# 000_BBB_Pinouts.net
KiCad netlist of a schematic drawn in Altium Designer
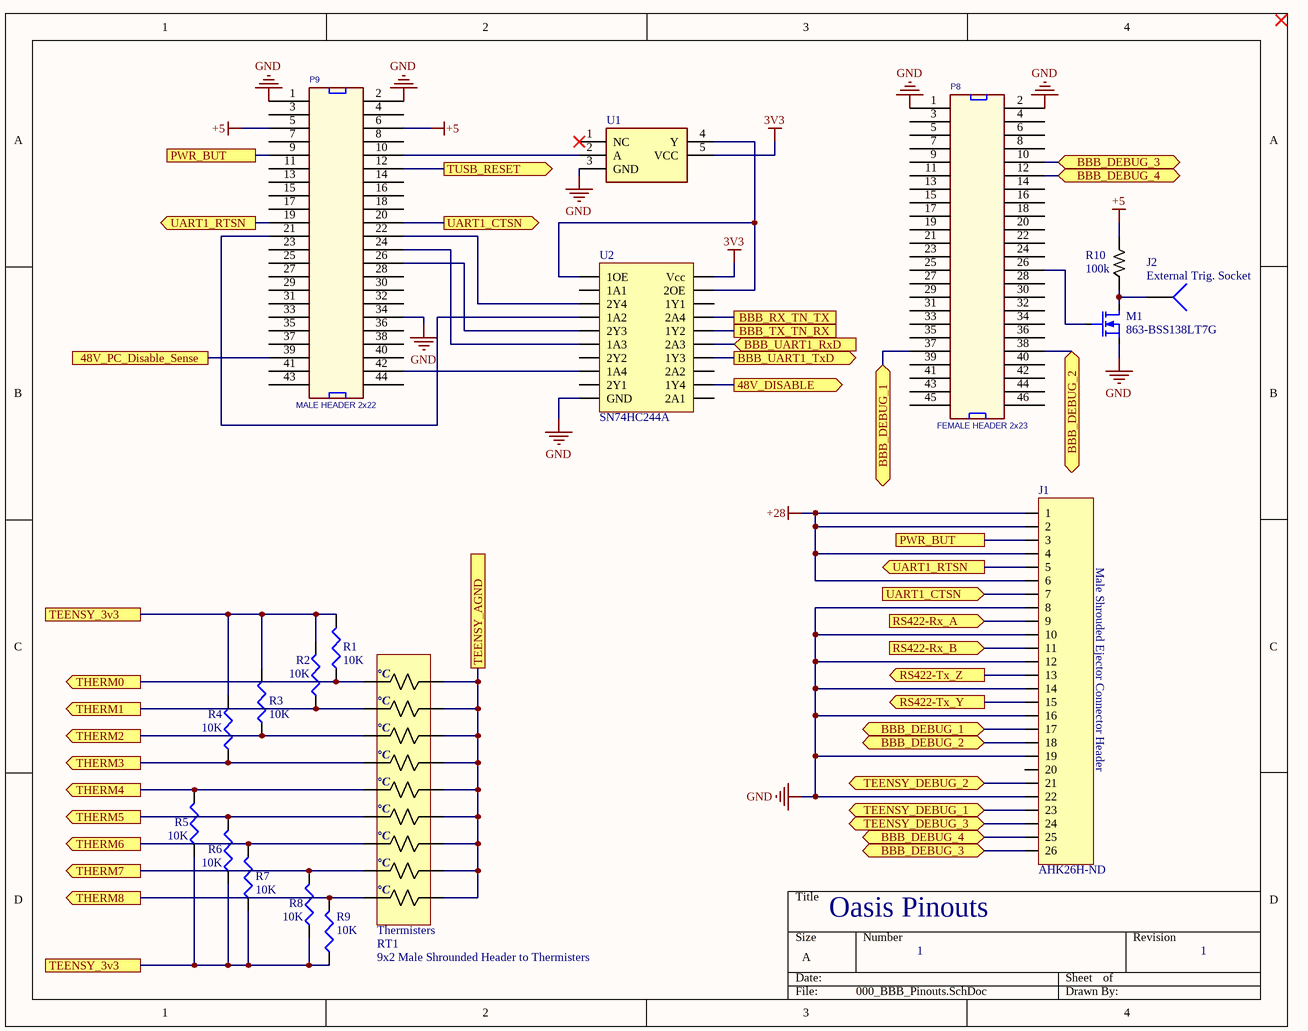
[diagram p0: 000_BBB_Pinouts.SchDoc]

(export (version "E")
  (design (tool "Eeschema 10.0.6"))
  (components
    (comp (ref "J1")
      (value "TE_5499922-6")
      (footprint "TE_5499922-6")
      (description "AMP-LATCH Universal Headers - 26 Pos")
      (fields (field (name "SUPPLIER PART NUMBER 1") "AHK26H-ND"))
      (libsource (lib "OASIS_COMPONENTS_SYMBOLS") (part "TE_5499922-6"))
    )
    (comp (ref "J2")
      (value "External Trig. Socket")
      (footprint "PIN1")
      (description "Socket")
      (fields (field (name "PUBLISHER") "Altium Limited"))
      (libsource (lib "Miscellaneous Connectors") (part "Socket"))
    )
    (comp (ref "M1")
      (value "BSS138LT7G")
      (footprint "SOT95P245X110-3N")
      (description "N-MOSFET for logic level switching")
      (fields (field (name "SUPPLIER PART NUMBER 1") "863-BSS138LT7G"))
      (libsource (lib "OASIS_COMPONENTS_SYMBOLS") (part "BSS138LT7G"))
    )
    (comp (ref "P8")
      (value "FEMALE HEADER 2x23")
      (footprint "MAJOR-TSHC-123-D-03_V_FLIPPED")
      (description "2x23 Female Pin header, 2.54mm, gold plated")
      (fields
        (field (name "MANUFACTURER") "Sullins Connector Solutions")
        (field (name "MANUFACTURER PART NUMBER") "PPPC232LFBN-RC")
      )
      (libsource (lib "OASIS_COMPONENTS_SYMBOLS") (part "HDR_46_F_2_0.1_0.1"))
    )
    (comp (ref "P9")
      (value "MALE HEADER 2x22")
      (footprint "MAJOR-TSHC-123-D-03_V_TRIMMED")
      (description "2x22 Male Pin header, 2.54mm, gold plated")
      (fields
        (field (name "MANUFACTURER") "Sullins Connector Solutions")
        (field (name "MANUFACTURER PART NUMBER") "PPPC232LFBN-RC")
      )
      (libsource (lib "OASIS_COMPONENTS_SYMBOLS") (part "HDR_44_M_TRIMMED"))
    )
    (comp (ref "R1")
      (value "10K")
      (footprint "Imperial0603_RES")
      (description "10K resistor, Thermister Pullup Resistor")
      (fields (field (name "Comment") "10K Resistor") (field (name "PUBLISHER") "Altium Limited"))
      (libsource (lib "OASIS_COMPONENTS_SYMBOLS") (part "RN731JTTD1002F10"))
    )
    (comp (ref "R2")
      (value "10K")
      (footprint "Imperial0603_RES")
      (description "10K resistor, Thermister Pullup Resistor")
      (fields (field (name "Comment") "10K Resistor") (field (name "PUBLISHER") "Altium Limited"))
      (libsource (lib "OASIS_COMPONENTS_SYMBOLS") (part "RN731JTTD1002F10"))
    )
    (comp (ref "R3")
      (value "10K")
      (footprint "Imperial0603_RES")
      (description "10K resistor, Thermister Pullup Resistor")
      (fields (field (name "Comment") "10K Resistor") (field (name "PUBLISHER") "Altium Limited"))
      (libsource (lib "OASIS_COMPONENTS_SYMBOLS") (part "RN731JTTD1002F10"))
    )
    (comp (ref "R4")
      (value "10K")
      (footprint "Imperial0603_RES")
      (description "10K resistor, Thermister Pullup Resistor")
      (fields (field (name "Comment") "10K Resistor") (field (name "PUBLISHER") "Altium Limited"))
      (libsource (lib "OASIS_COMPONENTS_SYMBOLS") (part "RN731JTTD1002F10"))
    )
    (comp (ref "R5")
      (value "10K")
      (footprint "Imperial0603_RES")
      (description "10K resistor, Thermister Pullup Resistor")
      (fields (field (name "Comment") "10K Resistor") (field (name "PUBLISHER") "Altium Limited"))
      (libsource (lib "OASIS_COMPONENTS_SYMBOLS") (part "RN731JTTD1002F10"))
    )
    (comp (ref "R6")
      (value "10K")
      (footprint "Imperial0603_RES")
      (description "10K resistor, Thermister Pullup Resistor")
      (fields (field (name "Comment") "10K Resistor") (field (name "PUBLISHER") "Altium Limited"))
      (libsource (lib "OASIS_COMPONENTS_SYMBOLS") (part "RN731JTTD1002F10"))
    )
    (comp (ref "R7")
      (value "10K")
      (footprint "Imperial0603_RES")
      (description "10K resistor, Thermister Pullup Resistor")
      (fields (field (name "Comment") "10K Resistor") (field (name "PUBLISHER") "Altium Limited"))
      (libsource (lib "OASIS_COMPONENTS_SYMBOLS") (part "RN731JTTD1002F10"))
    )
    (comp (ref "R8")
      (value "10K")
      (footprint "Imperial0603_RES")
      (description "10K resistor, Thermister Pullup Resistor")
      (fields (field (name "Comment") "10K Resistor") (field (name "PUBLISHER") "Altium Limited"))
      (libsource (lib "OASIS_COMPONENTS_SYMBOLS") (part "RN731JTTD1002F10"))
    )
    (comp (ref "R9")
      (value "10K")
      (footprint "Imperial0603_RES")
      (description "10K resistor, Thermister Pullup Resistor")
      (fields (field (name "Comment") "10K Resistor") (field (name "PUBLISHER") "Altium Limited"))
      (libsource (lib "OASIS_COMPONENTS_SYMBOLS") (part "RN731JTTD1002F10"))
    )
    (comp (ref "R10")
      (value "100k")
      (footprint "Imperial0603_RES")
      (description "100 kOhm Resistor")
      (fields (field (name "Comment") "MCT06030E1003BP500"))
      (libsource (lib "OASIS_COMPONENTS_SYMBOLS") (part "MCT06030E1003BP500"))
    )
    (comp (ref "RT1")
      (value "NTC Thermister Array")
      (footprint "MOLEX 90130-1118")
      (description "NTC Thermisters to monitor temperature of box. On PCB this will be a pin header.")
      (libsource (lib "OASIS_COMPONENTS_SYMBOLS") (part "Thermisters"))
    )
    (comp (ref "U1")
      (value "single gate inverter")
      (footprint "SOT65P210X110-5N")
      (description "Inverter, single gate")
      (fields (field (name "MANUFACTURER_PART_NUMBER") "SN74AHC1G14DCK3"))
      (libsource (lib "OASIS_COMPONENTS_SYMBOLS") (part "SN74AHC1G14DCK3"))
    )
    (comp (ref "U2")
      (value "Tristate buffer")
      (footprint "SOP65P780X200-20N")
      (description "Tristate buffer for protecting the BBB during power down.")
      (fields (field (name "IC FAMILY") "SN74HC244A"))
      (libsource (lib "OASIS_COMPONENTS_SYMBOLS") (part "SN74HC244A"))
    )
  )
  (nets
    (net (code "1") (name "+5") (class "Default")
      (node (ref "P9") (pin "5") (pinfunction "3_5") (pintype "passive"))
      (node (ref "P9") (pin "6") (pinfunction "28_6") (pintype "passive"))
      (node (ref "R10") (pin "1") (pinfunction "1_1") (pintype "passive"))
    )
    (net (code "2") (name "+28") (class "Default")
      (node (ref "J1") (pin "1") (pinfunction "1_1") (pintype "passive"))
      (node (ref "J1") (pin "2") (pinfunction "2_2") (pintype "passive"))
      (node (ref "J1") (pin "4") (pinfunction "4_4") (pintype "passive"))
      (node (ref "J1") (pin "6") (pinfunction "6_6") (pintype "passive"))
    )
    (net (code "3") (name "/48V_DISABLE") (class "Default")
      (node (ref "U2") (pin "12") (pinfunction "1Y4_12") (pintype "passive"))
    )
    (net (code "4") (name "/48V_PC_Disable_Sense") (class "Default")
      (node (ref "P9") (pin "39") (pinfunction "20_39") (pintype "passive"))
    )
    (net (code "5") (name "/BBB_DEBUG_1") (class "Default")
      (node (ref "J1") (pin "17") (pinfunction "17_17") (pintype "passive"))
      (node (ref "P8") (pin "37") (pinfunction "19_37") (pintype "passive"))
    )
    (net (code "6") (name "/BBB_DEBUG_2") (class "Default")
      (node (ref "J1") (pin "18") (pinfunction "18_18") (pintype "passive"))
      (node (ref "P8") (pin "38") (pinfunction "44_38") (pintype "passive"))
    )
    (net (code "7") (name "/BBB_DEBUG_3") (class "Default")
      (node (ref "J1") (pin "26") (pinfunction "26_26") (pintype "passive"))
      (node (ref "P8") (pin "10") (pinfunction "30_10") (pintype "passive"))
    )
    (net (code "8") (name "/BBB_DEBUG_4") (class "Default")
      (node (ref "J1") (pin "25") (pinfunction "25_25") (pintype "passive"))
      (node (ref "P8") (pin "12") (pinfunction "31_12") (pintype "passive"))
    )
    (net (code "9") (name "/BBB_RX_TN_TX") (class "Default")
      (node (ref "U2") (pin "17") (pinfunction "2A4_17") (pintype "passive"))
    )
    (net (code "10") (name "/BBB_TX_TN_RX") (class "Default")
      (node (ref "U2") (pin "16") (pinfunction "1Y2_16") (pintype "passive"))
    )
    (net (code "11") (name "/BBB_UART1_RxD") (class "Default")
      (node (ref "U2") (pin "15") (pinfunction "2A3_15") (pintype "passive"))
    )
    (net (code "12") (name "/BBB_UART1_TxD") (class "Default")
      (node (ref "U2") (pin "14") (pinfunction "1Y3_14") (pintype "passive"))
    )
    (net (code "13") (name "/PWR_BUT") (class "Default")
      (node (ref "J1") (pin "3") (pinfunction "3_3") (pintype "passive"))
      (node (ref "P9") (pin "9") (pinfunction "5_9") (pintype "passive"))
    )
    (net (code "14") (name "/RS422-Rx_A") (class "Default")
      (node (ref "J1") (pin "9") (pinfunction "9_9") (pintype "passive"))
    )
    (net (code "15") (name "/RS422-Rx_B") (class "Default")
      (node (ref "J1") (pin "11") (pinfunction "11_11") (pintype "passive"))
    )
    (net (code "16") (name "/RS422-Tx_Y") (class "Default")
      (node (ref "J1") (pin "15") (pinfunction "15_15") (pintype "passive"))
    )
    (net (code "17") (name "/RS422-Tx_Z") (class "Default")
      (node (ref "J1") (pin "13") (pinfunction "13_13") (pintype "passive"))
    )
    (net (code "18") (name "/TEENSY_3v3") (class "Default")
      (node (ref "R1") (pin "2") (pinfunction "2_2") (pintype "passive"))
      (node (ref "R2") (pin "2") (pinfunction "2_2") (pintype "passive"))
      (node (ref "R3") (pin "2") (pinfunction "2_2") (pintype "passive"))
      (node (ref "R4") (pin "2") (pinfunction "2_2") (pintype "passive"))
      (node (ref "R5") (pin "1") (pinfunction "1_1") (pintype "passive"))
      (node (ref "R6") (pin "2") (pinfunction "2_2") (pintype "passive"))
      (node (ref "R7") (pin "2") (pinfunction "2_2") (pintype "passive"))
      (node (ref "R8") (pin "2") (pinfunction "2_2") (pintype "passive"))
      (node (ref "R9") (pin "2") (pinfunction "2_2") (pintype "passive"))
    )
    (net (code "19") (name "/TEENSY_AGND") (class "Default")
      (node (ref "RT1") (pin "10") (pinfunction "10_10") (pintype "passive"))
      (node (ref "RT1") (pin "12") (pinfunction "12_12") (pintype "passive"))
      (node (ref "RT1") (pin "14") (pinfunction "14_14") (pintype "passive"))
      (node (ref "RT1") (pin "16") (pinfunction "16_16") (pintype "passive"))
      (node (ref "RT1") (pin "18") (pinfunction "18_18") (pintype "passive"))
      (node (ref "RT1") (pin "2") (pinfunction "2_2") (pintype "passive"))
      (node (ref "RT1") (pin "4") (pinfunction "4_4") (pintype "passive"))
      (node (ref "RT1") (pin "6") (pinfunction "6_6") (pintype "passive"))
      (node (ref "RT1") (pin "8") (pinfunction "8_8") (pintype "passive"))
    )
    (net (code "20") (name "/TEENSY_DEBUG_1") (class "Default")
      (node (ref "J1") (pin "23") (pinfunction "23_23") (pintype "passive"))
    )
    (net (code "21") (name "/TEENSY_DEBUG_2") (class "Default")
      (node (ref "J1") (pin "21") (pinfunction "21_21") (pintype "passive"))
    )
    (net (code "22") (name "/TEENSY_DEBUG_3") (class "Default")
      (node (ref "J1") (pin "24") (pinfunction "24_24") (pintype "passive"))
    )
    (net (code "23") (name "/THERM0") (class "Default")
      (node (ref "R1") (pin "1") (pinfunction "1_1") (pintype "passive"))
      (node (ref "RT1") (pin "1") (pinfunction "1_1") (pintype "passive"))
    )
    (net (code "24") (name "/THERM1") (class "Default")
      (node (ref "R2") (pin "1") (pinfunction "1_1") (pintype "passive"))
      (node (ref "RT1") (pin "3") (pinfunction "3_3") (pintype "passive"))
    )
    (net (code "25") (name "/THERM2") (class "Default")
      (node (ref "R3") (pin "1") (pinfunction "1_1") (pintype "passive"))
      (node (ref "RT1") (pin "5") (pinfunction "5_5") (pintype "passive"))
    )
    (net (code "26") (name "/THERM3") (class "Default")
      (node (ref "R4") (pin "1") (pinfunction "1_1") (pintype "passive"))
      (node (ref "RT1") (pin "7") (pinfunction "7_7") (pintype "passive"))
    )
    (net (code "27") (name "/THERM4") (class "Default")
      (node (ref "R5") (pin "2") (pinfunction "2_2") (pintype "passive"))
      (node (ref "RT1") (pin "9") (pinfunction "9_9") (pintype "passive"))
    )
    (net (code "28") (name "/THERM5") (class "Default")
      (node (ref "R6") (pin "1") (pinfunction "1_1") (pintype "passive"))
      (node (ref "RT1") (pin "11") (pinfunction "11_11") (pintype "passive"))
    )
    (net (code "29") (name "/THERM6") (class "Default")
      (node (ref "R7") (pin "1") (pinfunction "1_1") (pintype "passive"))
      (node (ref "RT1") (pin "13") (pinfunction "13_13") (pintype "passive"))
    )
    (net (code "30") (name "/THERM7") (class "Default")
      (node (ref "R8") (pin "1") (pinfunction "1_1") (pintype "passive"))
      (node (ref "RT1") (pin "15") (pinfunction "15_15") (pintype "passive"))
    )
    (net (code "31") (name "/THERM8") (class "Default")
      (node (ref "R9") (pin "1") (pinfunction "1_1") (pintype "passive"))
      (node (ref "RT1") (pin "17") (pinfunction "17_17") (pintype "passive"))
    )
    (net (code "32") (name "/TUSB_RESET") (class "Default")
      (node (ref "P9") (pin "12") (pinfunction "31_12") (pintype "passive"))
    )
    (net (code "33") (name "/UART1_CTSN") (class "Default")
      (node (ref "J1") (pin "7") (pinfunction "7_7") (pintype "passive"))
      (node (ref "P9") (pin "20") (pinfunction "35_20") (pintype "passive"))
    )
    (net (code "34") (name "/UART1_RTSN") (class "Default")
      (node (ref "J1") (pin "5") (pinfunction "5_5") (pintype "passive"))
      (node (ref "P9") (pin "19") (pinfunction "10_19") (pintype "passive"))
    )
    (net (code "35") (name "3V3") (class "Default")
      (node (ref "U1") (pin "5") (pinfunction "VCC_5") (pintype "passive"))
      (node (ref "U2") (pin "20") (pinfunction "Vcc_20") (pintype "passive"))
    )
    (net (code "36") (name "GND") (class "Default")
      (node (ref "J1") (pin "10") (pinfunction "10_10") (pintype "passive"))
      (node (ref "J1") (pin "12") (pinfunction "12_12") (pintype "passive"))
      (node (ref "J1") (pin "14") (pinfunction "14_14") (pintype "passive"))
      (node (ref "J1") (pin "16") (pinfunction "16_16") (pintype "passive"))
      (node (ref "J1") (pin "19") (pinfunction "19_19") (pintype "passive"))
      (node (ref "J1") (pin "22") (pinfunction "22_22") (pintype "passive"))
      (node (ref "J1") (pin "8") (pinfunction "8_8") (pintype "passive"))
      (node (ref "M1") (pin "2") (pinfunction "S_2") (pintype "passive"))
      (node (ref "P8") (pin "1") (pinfunction "1_1") (pintype "passive"))
      (node (ref "P8") (pin "2") (pinfunction "26_2") (pintype "passive"))
      (node (ref "P9") (pin "1") (pinfunction "1_1") (pintype "passive"))
      (node (ref "P9") (pin "2") (pinfunction "26_2") (pintype "passive"))
      (node (ref "P9") (pin "34") (pinfunction "42_34") (pintype "passive"))
      (node (ref "U1") (pin "3") (pinfunction "GND_3") (pintype "passive"))
      (node (ref "U2") (pin "10") (pinfunction "GND_10") (pintype "passive"))
    )
    (net (code "37") (name "Net-(M1-D)") (class "Default")
      (node (ref "J2") (pin "1") (pinfunction "1_1") (pintype "passive"))
      (node (ref "M1") (pin "3") (pinfunction "D_3") (pintype "passive"))
      (node (ref "R10") (pin "2") (pinfunction "2_2") (pintype "passive"))
    )
    (net (code "38") (name "Net-(M1-G)") (class "Default")
      (node (ref "M1") (pin "1") (pinfunction "G_1") (pintype "passive"))
      (node (ref "P8") (pin "26") (pinfunction "38_26") (pintype "passive"))
    )
    (net (code "39") (name "Net-(P9-11)") (class "Default")
      (node (ref "P9") (pin "21") (pinfunction "11_21") (pintype "passive"))
      (node (ref "U2") (pin "4") (pinfunction "1A2_4") (pintype "passive"))
    )
    (net (code "40") (name "Net-(P9-30)") (class "Default")
      (node (ref "P9") (pin "10") (pinfunction "30_10") (pintype "passive"))
      (node (ref "U1") (pin "2") (pinfunction "A_2") (pintype "passive"))
    )
    (net (code "41") (name "Net-(P9-36)") (class "Default")
      (node (ref "P9") (pin "22") (pinfunction "36_22") (pintype "passive"))
      (node (ref "U2") (pin "3") (pinfunction "2Y4_3") (pintype "passive"))
    )
    (net (code "42") (name "Net-(P9-37)") (class "Default")
      (node (ref "P9") (pin "24") (pinfunction "37_24") (pintype "passive"))
      (node (ref "U2") (pin "6") (pinfunction "1A3_6") (pintype "passive"))
    )
    (net (code "43") (name "Net-(P9-38)") (class "Default")
      (node (ref "P9") (pin "26") (pinfunction "38_26") (pintype "passive"))
      (node (ref "U2") (pin "5") (pinfunction "2Y3_5") (pintype "passive"))
    )
    (net (code "44") (name "Net-(P9-46)") (class "Default")
      (node (ref "P9") (pin "42") (pinfunction "46_42") (pintype "passive"))
      (node (ref "U2") (pin "8") (pinfunction "1A4_8") (pintype "passive"))
    )
    (net (code "45") (name "Net-(U1-Y)") (class "Default")
      (node (ref "U1") (pin "4") (pinfunction "Y_4") (pintype "passive"))
      (node (ref "U2") (pin "1") (pinfunction "1OE_1") (pintype "passive"))
      (node (ref "U2") (pin "19") (pinfunction "2OE_19") (pintype "passive"))
    )
    (net (code "46") (name "unconnected-(J1-Pad20)") (class "Default")
      (node (ref "J1") (pin "20") (pinfunction "20_20") (pintype "passive"))
    )
    (net (code "47") (name "unconnected-(P8-2-Pad3)") (class "Default")
      (node (ref "P8") (pin "3") (pinfunction "2_3") (pintype "passive"))
    )
    (net (code "48") (name "unconnected-(P8-3-Pad5)") (class "Default")
      (node (ref "P8") (pin "5") (pinfunction "3_5") (pintype "passive"))
    )
    (net (code "49") (name "unconnected-(P8-4-Pad7)") (class "Default")
      (node (ref "P8") (pin "7") (pinfunction "4_7") (pintype "passive"))
    )
    (net (code "50") (name "unconnected-(P8-5-Pad9)") (class "Default")
      (node (ref "P8") (pin "9") (pinfunction "5_9") (pintype "passive"))
    )
    (net (code "51") (name "unconnected-(P8-6-Pad11)") (class "Default")
      (node (ref "P8") (pin "11") (pinfunction "6_11") (pintype "passive"))
    )
    (net (code "52") (name "unconnected-(P8-7-Pad13)") (class "Default")
      (node (ref "P8") (pin "13") (pinfunction "7_13") (pintype "passive"))
    )
    (net (code "53") (name "unconnected-(P8-8-Pad15)") (class "Default")
      (node (ref "P8") (pin "15") (pinfunction "8_15") (pintype "passive"))
    )
    (net (code "54") (name "unconnected-(P8-9-Pad17)") (class "Default")
      (node (ref "P8") (pin "17") (pinfunction "9_17") (pintype "passive"))
    )
    (net (code "55") (name "unconnected-(P8-10-Pad19)") (class "Default")
      (node (ref "P8") (pin "19") (pinfunction "10_19") (pintype "passive"))
    )
    (net (code "56") (name "unconnected-(P8-11-Pad21)") (class "Default")
      (node (ref "P8") (pin "21") (pinfunction "11_21") (pintype "passive"))
    )
    (net (code "57") (name "unconnected-(P8-12-Pad23)") (class "Default")
      (node (ref "P8") (pin "23") (pinfunction "12_23") (pintype "passive"))
    )
    (net (code "58") (name "unconnected-(P8-13-Pad25)") (class "Default")
      (node (ref "P8") (pin "25") (pinfunction "13_25") (pintype "passive"))
    )
    (net (code "59") (name "unconnected-(P8-14-Pad27)") (class "Default")
      (node (ref "P8") (pin "27") (pinfunction "14_27") (pintype "passive"))
    )
    (net (code "60") (name "unconnected-(P8-15-Pad29)") (class "Default")
      (node (ref "P8") (pin "29") (pinfunction "15_29") (pintype "passive"))
    )
    (net (code "61") (name "unconnected-(P8-16-Pad31)") (class "Default")
      (node (ref "P8") (pin "31") (pinfunction "16_31") (pintype "passive"))
    )
    (net (code "62") (name "unconnected-(P8-17-Pad33)") (class "Default")
      (node (ref "P8") (pin "33") (pinfunction "17_33") (pintype "passive"))
    )
    (net (code "63") (name "unconnected-(P8-18-Pad35)") (class "Default")
      (node (ref "P8") (pin "35") (pinfunction "18_35") (pintype "passive"))
    )
    (net (code "64") (name "unconnected-(P8-20-Pad39)") (class "Default")
      (node (ref "P8") (pin "39") (pinfunction "20_39") (pintype "passive"))
    )
    (net (code "65") (name "unconnected-(P8-21-Pad41)") (class "Default")
      (node (ref "P8") (pin "41") (pinfunction "21_41") (pintype "passive"))
    )
    (net (code "66") (name "unconnected-(P8-22-Pad43)") (class "Default")
      (node (ref "P8") (pin "43") (pinfunction "22_43") (pintype "passive"))
    )
    (net (code "67") (name "unconnected-(P8-23-Pad45)") (class "Default")
      (node (ref "P8") (pin "45") (pinfunction "23_45") (pintype "passive"))
    )
    (net (code "68") (name "unconnected-(P8-27-Pad4)") (class "Default")
      (node (ref "P8") (pin "4") (pinfunction "27_4") (pintype "passive"))
    )
    (net (code "69") (name "unconnected-(P8-28-Pad6)") (class "Default")
      (node (ref "P8") (pin "6") (pinfunction "28_6") (pintype "passive"))
    )
    (net (code "70") (name "unconnected-(P8-29-Pad8)") (class "Default")
      (node (ref "P8") (pin "8") (pinfunction "29_8") (pintype "passive"))
    )
    (net (code "71") (name "unconnected-(P8-32-Pad14)") (class "Default")
      (node (ref "P8") (pin "14") (pinfunction "32_14") (pintype "passive"))
    )
    (net (code "72") (name "unconnected-(P8-33-Pad16)") (class "Default")
      (node (ref "P8") (pin "16") (pinfunction "33_16") (pintype "passive"))
    )
    (net (code "73") (name "unconnected-(P8-34-Pad18)") (class "Default")
      (node (ref "P8") (pin "18") (pinfunction "34_18") (pintype "passive"))
    )
    (net (code "74") (name "unconnected-(P8-35-Pad20)") (class "Default")
      (node (ref "P8") (pin "20") (pinfunction "35_20") (pintype "passive"))
    )
    (net (code "75") (name "unconnected-(P8-36-Pad22)") (class "Default")
      (node (ref "P8") (pin "22") (pinfunction "36_22") (pintype "passive"))
    )
    (net (code "76") (name "unconnected-(P8-37-Pad24)") (class "Default")
      (node (ref "P8") (pin "24") (pinfunction "37_24") (pintype "passive"))
    )
    (net (code "77") (name "unconnected-(P8-39-Pad28)") (class "Default")
      (node (ref "P8") (pin "28") (pinfunction "39_28") (pintype "passive"))
    )
    (net (code "78") (name "unconnected-(P8-40-Pad30)") (class "Default")
      (node (ref "P8") (pin "30") (pinfunction "40_30") (pintype "passive"))
    )
    (net (code "79") (name "unconnected-(P8-41-Pad32)") (class "Default")
      (node (ref "P8") (pin "32") (pinfunction "41_32") (pintype "passive"))
    )
    (net (code "80") (name "unconnected-(P8-42-Pad34)") (class "Default")
      (node (ref "P8") (pin "34") (pinfunction "42_34") (pintype "passive"))
    )
    (net (code "81") (name "unconnected-(P8-43-Pad36)") (class "Default")
      (node (ref "P8") (pin "36") (pinfunction "43_36") (pintype "passive"))
    )
    (net (code "82") (name "unconnected-(P8-45-Pad40)") (class "Default")
      (node (ref "P8") (pin "40") (pinfunction "45_40") (pintype "passive"))
    )
    (net (code "83") (name "unconnected-(P8-46-Pad42)") (class "Default")
      (node (ref "P8") (pin "42") (pinfunction "46_42") (pintype "passive"))
    )
    (net (code "84") (name "unconnected-(P8-47-Pad44)") (class "Default")
      (node (ref "P8") (pin "44") (pinfunction "47_44") (pintype "passive"))
    )
    (net (code "85") (name "unconnected-(P8-48-Pad46)") (class "Default")
      (node (ref "P8") (pin "46") (pinfunction "48_46") (pintype "passive"))
    )
    (net (code "86") (name "unconnected-(P9-2-Pad3)") (class "Default")
      (node (ref "P9") (pin "3") (pinfunction "2_3") (pintype "passive"))
    )
    (net (code "87") (name "unconnected-(P9-4-Pad7)") (class "Default")
      (node (ref "P9") (pin "7") (pinfunction "4_7") (pintype "passive"))
    )
    (net (code "88") (name "unconnected-(P9-6-Pad11)") (class "Default")
      (node (ref "P9") (pin "11") (pinfunction "6_11") (pintype "passive"))
    )
    (net (code "89") (name "unconnected-(P9-7-Pad13)") (class "Default")
      (node (ref "P9") (pin "13") (pinfunction "7_13") (pintype "passive"))
    )
    (net (code "90") (name "unconnected-(P9-8-Pad15)") (class "Default")
      (node (ref "P9") (pin "15") (pinfunction "8_15") (pintype "passive"))
    )
    (net (code "91") (name "unconnected-(P9-9-Pad17)") (class "Default")
      (node (ref "P9") (pin "17") (pinfunction "9_17") (pintype "passive"))
    )
    (net (code "92") (name "unconnected-(P9-12-Pad23)") (class "Default")
      (node (ref "P9") (pin "23") (pinfunction "12_23") (pintype "passive"))
    )
    (net (code "93") (name "unconnected-(P9-13-Pad25)") (class "Default")
      (node (ref "P9") (pin "25") (pinfunction "13_25") (pintype "passive"))
    )
    (net (code "94") (name "unconnected-(P9-14-Pad27)") (class "Default")
      (node (ref "P9") (pin "27") (pinfunction "14_27") (pintype "passive"))
    )
    (net (code "95") (name "unconnected-(P9-15-Pad29)") (class "Default")
      (node (ref "P9") (pin "29") (pinfunction "15_29") (pintype "passive"))
    )
    (net (code "96") (name "unconnected-(P9-16-Pad31)") (class "Default")
      (node (ref "P9") (pin "31") (pinfunction "16_31") (pintype "passive"))
    )
    (net (code "97") (name "unconnected-(P9-17-Pad33)") (class "Default")
      (node (ref "P9") (pin "33") (pinfunction "17_33") (pintype "passive"))
    )
    (net (code "98") (name "unconnected-(P9-18-Pad35)") (class "Default")
      (node (ref "P9") (pin "35") (pinfunction "18_35") (pintype "passive"))
    )
    (net (code "99") (name "unconnected-(P9-19-Pad37)") (class "Default")
      (node (ref "P9") (pin "37") (pinfunction "19_37") (pintype "passive"))
    )
    (net (code "100") (name "unconnected-(P9-21-Pad41)") (class "Default")
      (node (ref "P9") (pin "41") (pinfunction "21_41") (pintype "passive"))
    )
    (net (code "101") (name "unconnected-(P9-22-Pad43)") (class "Default")
      (node (ref "P9") (pin "43") (pinfunction "22_43") (pintype "passive"))
    )
    (net (code "102") (name "unconnected-(P9-27-Pad4)") (class "Default")
      (node (ref "P9") (pin "4") (pinfunction "27_4") (pintype "passive"))
    )
    (net (code "103") (name "unconnected-(P9-29-Pad8)") (class "Default")
      (node (ref "P9") (pin "8") (pinfunction "29_8") (pintype "passive"))
    )
    (net (code "104") (name "unconnected-(P9-32-Pad14)") (class "Default")
      (node (ref "P9") (pin "14") (pinfunction "32_14") (pintype "passive"))
    )
    (net (code "105") (name "unconnected-(P9-33-Pad16)") (class "Default")
      (node (ref "P9") (pin "16") (pinfunction "33_16") (pintype "passive"))
    )
    (net (code "106") (name "unconnected-(P9-34-Pad18)") (class "Default")
      (node (ref "P9") (pin "18") (pinfunction "34_18") (pintype "passive"))
    )
    (net (code "107") (name "unconnected-(P9-39-Pad28)") (class "Default")
      (node (ref "P9") (pin "28") (pinfunction "39_28") (pintype "passive"))
    )
    (net (code "108") (name "unconnected-(P9-40-Pad30)") (class "Default")
      (node (ref "P9") (pin "30") (pinfunction "40_30") (pintype "passive"))
    )
    (net (code "109") (name "unconnected-(P9-41-Pad32)") (class "Default")
      (node (ref "P9") (pin "32") (pinfunction "41_32") (pintype "passive"))
    )
    (net (code "110") (name "unconnected-(P9-43-Pad36)") (class "Default")
      (node (ref "P9") (pin "36") (pinfunction "43_36") (pintype "passive"))
    )
    (net (code "111") (name "unconnected-(P9-44-Pad38)") (class "Default")
      (node (ref "P9") (pin "38") (pinfunction "44_38") (pintype "passive"))
    )
    (net (code "112") (name "unconnected-(P9-45-Pad40)") (class "Default")
      (node (ref "P9") (pin "40") (pinfunction "45_40") (pintype "passive"))
    )
    (net (code "113") (name "unconnected-(P9-47-Pad44)") (class "Default")
      (node (ref "P9") (pin "44") (pinfunction "47_44") (pintype "passive"))
    )
    (net (code "114") (name "unconnected-(U1-NC-Pad1)") (class "Default")
      (node (ref "U1") (pin "1") (pinfunction "NC_1") (pintype "passive+no_connect"))
    )
    (net (code "115") (name "unconnected-(U2-1A1-Pad2)") (class "Default")
      (node (ref "U2") (pin "2") (pinfunction "1A1_2") (pintype "passive"))
    )
    (net (code "116") (name "unconnected-(U2-1Y1-Pad18)") (class "Default")
      (node (ref "U2") (pin "18") (pinfunction "1Y1_18") (pintype "passive"))
    )
    (net (code "117") (name "unconnected-(U2-2A1-Pad11)") (class "Default")
      (node (ref "U2") (pin "11") (pinfunction "2A1_11") (pintype "passive"))
    )
    (net (code "118") (name "unconnected-(U2-2A2-Pad13)") (class "Default")
      (node (ref "U2") (pin "13") (pinfunction "2A2_13") (pintype "passive"))
    )
    (net (code "119") (name "unconnected-(U2-2Y1-Pad9)") (class "Default")
      (node (ref "U2") (pin "9") (pinfunction "2Y1_9") (pintype "passive"))
    )
    (net (code "120") (name "unconnected-(U2-2Y2-Pad7)") (class "Default")
      (node (ref "U2") (pin "7") (pinfunction "2Y2_7") (pintype "passive"))
    )
  )
)
